# CamController3.net
KiCad netlist of a schematic drawn in Altium Designer
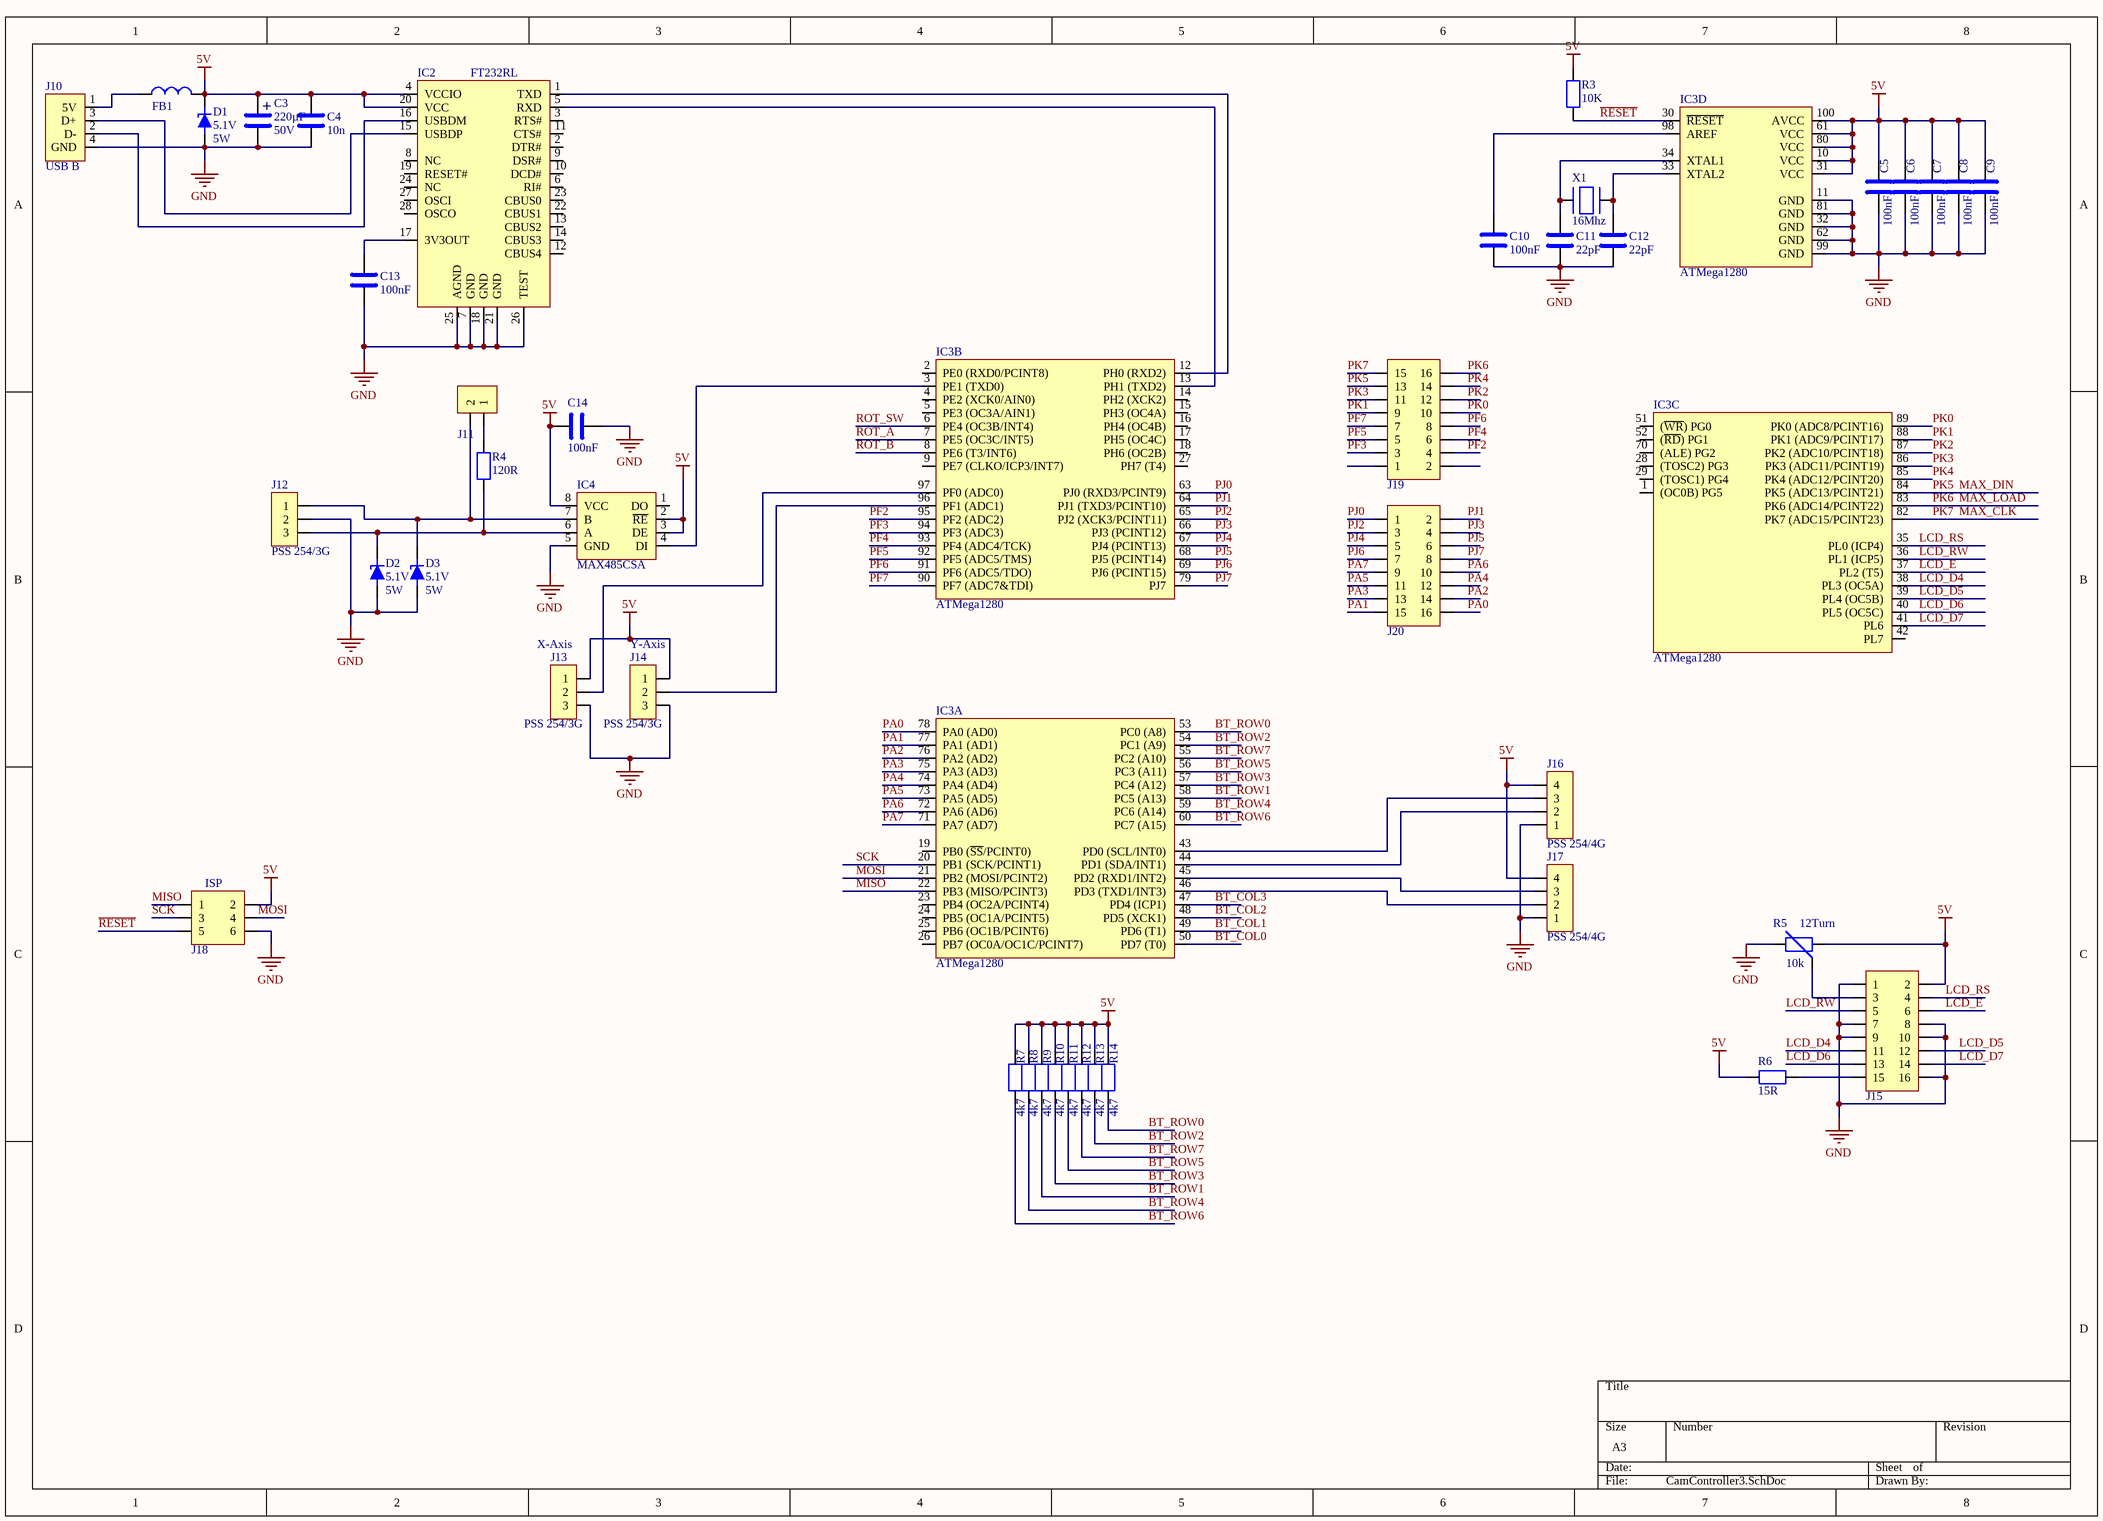
[diagram p0: CamController3.SchDoc]

(export (version "E")
  (design (tool "Eeschema 10.0.6"))
  (components
    (comp (ref "C3")
      (value "220µF")
      (footprint "RM5D125H20")
      (description "nichicon")
      (fields (field (name "VOLTAGE") "50V") (field (name "Comment") "Elko_220uF_50V"))
      (libsource (lib "elkos") (part "Elko_220uF_50V"))
    )
    (comp (ref "C4")
      (value "10n")
      (footprint "0805")
      (description "10nF 50V MLCC 0805")
      (fields (field (name "VOLTAGE") "50V"))
      (libsource (lib "capacitors") (part "10nF 50V MLCC 0805"))
    )
    (comp (ref "C5")
      (value "100nF")
      (footprint "0805")
      (description "100nF 50V MLCC 0805")
      (fields (field (name "VOLTAGE") "50V"))
      (libsource (lib "capacitors") (part "100nF 50V MLCC 0805"))
    )
    (comp (ref "C6")
      (value "100nF")
      (footprint "0805")
      (description "100nF 50V MLCC 0805")
      (fields (field (name "VOLTAGE") "50V"))
      (libsource (lib "capacitors") (part "100nF 50V MLCC 0805"))
    )
    (comp (ref "C7")
      (value "100nF")
      (footprint "0805")
      (description "100nF 50V MLCC 0805")
      (fields (field (name "VOLTAGE") "50V"))
      (libsource (lib "capacitors") (part "100nF 50V MLCC 0805"))
    )
    (comp (ref "C8")
      (value "100nF")
      (footprint "0805")
      (description "100nF 50V MLCC 0805")
      (fields (field (name "VOLTAGE") "50V"))
      (libsource (lib "capacitors") (part "100nF 50V MLCC 0805"))
    )
    (comp (ref "C9")
      (value "100nF")
      (footprint "0805")
      (description "100nF 50V MLCC 0805")
      (fields (field (name "VOLTAGE") "50V"))
      (libsource (lib "capacitors") (part "100nF 50V MLCC 0805"))
    )
    (comp (ref "C10")
      (value "100nF")
      (footprint "0805")
      (description "100nF 50V MLCC 0805")
      (fields (field (name "VOLTAGE") "50V"))
      (libsource (lib "capacitors") (part "100nF 50V MLCC 0805"))
    )
    (comp (ref "C11")
      (value "22pF")
      (footprint "0805")
      (description "22pF 50V MLCC 0805")
      (fields (field (name "VOLTAGE") "50V"))
      (libsource (lib "capacitors") (part "22pF 50V MLCC 0805"))
    )
    (comp (ref "C12")
      (value "22pF")
      (footprint "0805")
      (description "22pF 50V MLCC 0805")
      (fields (field (name "VOLTAGE") "50V"))
      (libsource (lib "capacitors") (part "22pF 50V MLCC 0805"))
    )
    (comp (ref "C13")
      (value "100nF")
      (footprint "0805")
      (description "100nF 50V MLCC 0805")
      (fields (field (name "VOLTAGE") "50V"))
      (libsource (lib "capacitors") (part "100nF 50V MLCC 0805"))
    )
    (comp (ref "C14")
      (value "100nF")
      (footprint "0805")
      (description "100nF 50V MLCC 0805")
      (fields (field (name "VOLTAGE") "50V"))
      (libsource (lib "capacitors") (part "100nF 50V MLCC 0805"))
    )
    (comp (ref "D1")
      (value "ZD-5W 5,1V")
      (footprint "DO-204AF")
      (fields (field (name "VOLTAGE") "5.1V") (field (name "POWER") "5W"))
      (libsource (lib "diodes") (part "ZD-5W 5,1V"))
    )
    (comp (ref "D2")
      (value "ZD-5W 5,1V")
      (footprint "DO-204AF")
      (fields (field (name "VOLTAGE") "5.1V") (field (name "POWER") "5W"))
      (libsource (lib "diodes") (part "ZD-5W 5,1V"))
    )
    (comp (ref "D3")
      (value "ZD-5W 5,1V")
      (footprint "DO-204AF")
      (fields (field (name "VOLTAGE") "5.1V") (field (name "POWER") "5W"))
      (libsource (lib "diodes") (part "ZD-5W 5,1V"))
    )
    (comp (ref "FB1")
      (value "Feritbead")
      (footprint "Ferritbead")
      (libsource (lib "misc") (part "Feritbead"))
    )
    (comp (ref "IC2")
      (value "FT232RL")
      (footprint "SSOP-28")
      (description "USB UART Bridge")
      (libsource (lib "misc") (part "FT 232 RL"))
    )
    (comp (ref "IC3")
      (value "ATMega1280")
      (footprint "LQFP100")
      (libsource (lib "microcontroller") (part "ATmega1280"))
    )
    (comp (ref "IC4")
      (value "MAX485CSA")
      (footprint "SOIC8")
      (description "RS485 driver")
      (libsource (lib "misc") (part "MAX485CSA"))
    )
    (comp (ref "J10") (value "USB B") (footprint "USB_B") (libsource (lib "connectors_pc") (part "USB_B")))
    (comp (ref "J11")
      (value "SL 1X2G 2,54")
      (footprint "SL_1x2 2.54mm")
      (description "Stiftleiste 2pol 2.54mm")
      (libsource (lib "connectors_sl") (part "SL 1X2G 2,54"))
    )
    (comp (ref "J12")
      (value "PSS 254/3G")
      (footprint "PSS 3pol")
      (description "PSS 3pol wire-to-board-connector")
      (libsource (lib "connectors_pss") (part "PSS 254/3G"))
    )
    (comp (ref "J13")
      (value "PSS 254/3G")
      (footprint "PSS 3pol")
      (description "PSS 3pol wire-to-board-connector")
      (libsource (lib "connectors_pss") (part "PSS 254/3G"))
    )
    (comp (ref "J14")
      (value "PSS 254/3G")
      (footprint "PSS 3pol")
      (description "PSS 3pol wire-to-board-connector")
      (libsource (lib "connectors_pss") (part "PSS 254/3G"))
    )
    (comp (ref "J15")
      (value "Wannenstecker 16pol 2,54mm")
      (footprint "WSL16G")
      (libsource (lib "wannenstecker") (part "Wannenstecker 16pol 2,54mm"))
    )
    (comp (ref "J16")
      (value "PSS 254/4G")
      (footprint "PSS 4pol")
      (description "PSS 4pol wire-to-board-connector")
      (libsource (lib "connectors_pss") (part "PSS 254/4G"))
    )
    (comp (ref "J17")
      (value "PSS 254/4G")
      (footprint "PSS 4pol")
      (description "PSS 4pol wire-to-board-connector")
      (libsource (lib "connectors_pss") (part "PSS 254/4G"))
    )
    (comp (ref "J18")
      (value "Wannenstecker 6pol 2,54mm")
      (footprint "WSL6G")
      (libsource (lib "wannenstecker") (part "Wannenstecker 6pol 2,54mm"))
    )
    (comp (ref "J19")
      (value "Wannenstecker 16pol 2,54mm")
      (footprint "WSL16G")
      (libsource (lib "") (part "Wannenstecker 16pol 2,54mm_1"))
    )
    (comp (ref "J20")
      (value "Wannenstecker 16pol 2,54mm")
      (footprint "WSL16G")
      (libsource (lib "wannenstecker") (part "Wannenstecker 16pol 2,54mm"))
    )
    (comp (ref "R3")
      (value "10K")
      (footprint "res0805")
      (description "10K 125mW 0805")
      (fields (field (name "TOLERANCE") "1%"))
      (libsource (lib "resistors") (part "10K 125mW 0805"))
    )
    (comp (ref "R4")
      (value "120R")
      (footprint "res0805")
      (description "120R 125mW 0805")
      (fields (field (name "TOLERANCE") "1%"))
      (libsource (lib "resistors") (part "120R 125mW 0805"))
    )
    (comp (ref "R5")
      (value "12Turn")
      (footprint "64W")
      (description "trimmer 12turn")
      (fields (field (name "ALTIUM_VALUE") "10k"))
      (libsource (lib "trimmer") (part "64W-10K"))
    )
    (comp (ref "R6")
      (value "15R")
      (footprint "res0805")
      (description "15R 125mW 0805")
      (fields (field (name "TOLERANCE") "1%"))
      (libsource (lib "resistors") (part "15R 125mW 0805"))
    )
    (comp (ref "R7")
      (value "4k7")
      (footprint "res0805")
      (description "4k7 125mW 0805")
      (fields (field (name "TOLERANCE") "1%"))
      (libsource (lib "resistors") (part "4k7 125mW 0805"))
    )
    (comp (ref "R8")
      (value "4k7")
      (footprint "res0805")
      (description "4k7 125mW 0805")
      (fields (field (name "TOLERANCE") "1%"))
      (libsource (lib "resistors") (part "4k7 125mW 0805"))
    )
    (comp (ref "R9")
      (value "4k7")
      (footprint "res0805")
      (description "4k7 125mW 0805")
      (fields (field (name "TOLERANCE") "1%"))
      (libsource (lib "resistors") (part "4k7 125mW 0805"))
    )
    (comp (ref "R10")
      (value "4k7")
      (footprint "res0805")
      (description "4k7 125mW 0805")
      (fields (field (name "TOLERANCE") "1%"))
      (libsource (lib "resistors") (part "4k7 125mW 0805"))
    )
    (comp (ref "R11")
      (value "4k7")
      (footprint "res0805")
      (description "4k7 125mW 0805")
      (fields (field (name "TOLERANCE") "1%"))
      (libsource (lib "resistors") (part "4k7 125mW 0805"))
    )
    (comp (ref "R12")
      (value "4k7")
      (footprint "res0805")
      (description "4k7 125mW 0805")
      (fields (field (name "TOLERANCE") "1%"))
      (libsource (lib "resistors") (part "4k7 125mW 0805"))
    )
    (comp (ref "R13")
      (value "4k7")
      (footprint "res0805")
      (description "4k7 125mW 0805")
      (fields (field (name "TOLERANCE") "1%"))
      (libsource (lib "resistors") (part "4k7 125mW 0805"))
    )
    (comp (ref "R14")
      (value "4k7")
      (footprint "res0805")
      (description "4k7 125mW 0805")
      (fields (field (name "TOLERANCE") "1%"))
      (libsource (lib "resistors") (part "4k7 125mW 0805"))
    )
    (comp (ref "X1")
      (value "8Mhz_HC49U")
      (footprint "HC49")
      (description "8Mhz crystal resonator")
      (fields (field (name "FREQUENCY") "16Mhz"))
      (libsource (lib "crystals") (part "8Mhz_HC49U"))
    )
  )
  (nets
    (net (code "1") (name "/BT_COL0") (class "Default")
      (node (ref "IC3") (pin "50") (pinfunction "PD7_(T0)_50") (pintype "passive"))
    )
    (net (code "2") (name "/BT_COL1") (class "Default")
      (node (ref "IC3") (pin "49") (pinfunction "PD6_(T1)_49") (pintype "passive"))
    )
    (net (code "3") (name "/BT_COL2") (class "Default")
      (node (ref "IC3") (pin "48") (pinfunction "PD5_(XCK1)_48") (pintype "passive"))
    )
    (net (code "4") (name "/BT_COL3") (class "Default")
      (node (ref "IC3") (pin "47") (pinfunction "PD4_(ICP1)_47") (pintype "passive"))
    )
    (net (code "5") (name "/BT_ROW0") (class "Default")
      (node (ref "IC3") (pin "53") (pinfunction "PC0_(A8)_53") (pintype "passive"))
      (node (ref "R14") (pin "1") (pinfunction "1_1") (pintype "passive"))
    )
    (net (code "6") (name "/BT_ROW1") (class "Default")
      (node (ref "IC3") (pin "58") (pinfunction "PC5_(A13)_58") (pintype "passive"))
      (node (ref "R9") (pin "1") (pinfunction "1_1") (pintype "passive"))
    )
    (net (code "7") (name "/BT_ROW2") (class "Default")
      (node (ref "IC3") (pin "54") (pinfunction "PC1_(A9)_54") (pintype "passive"))
      (node (ref "R13") (pin "1") (pinfunction "1_1") (pintype "passive"))
    )
    (net (code "8") (name "/BT_ROW3") (class "Default")
      (node (ref "IC3") (pin "57") (pinfunction "PC4_(A12)_57") (pintype "passive"))
      (node (ref "R10") (pin "1") (pinfunction "1_1") (pintype "passive"))
    )
    (net (code "9") (name "/BT_ROW4") (class "Default")
      (node (ref "IC3") (pin "59") (pinfunction "PC6_(A14)_59") (pintype "passive"))
      (node (ref "R8") (pin "1") (pinfunction "1_1") (pintype "passive"))
    )
    (net (code "10") (name "/BT_ROW5") (class "Default")
      (node (ref "IC3") (pin "56") (pinfunction "PC3_(A11)_56") (pintype "passive"))
      (node (ref "R11") (pin "1") (pinfunction "1_1") (pintype "passive"))
    )
    (net (code "11") (name "/BT_ROW6") (class "Default")
      (node (ref "IC3") (pin "60") (pinfunction "PC7_(A15)_60") (pintype "passive"))
      (node (ref "R7") (pin "1") (pinfunction "1_1") (pintype "passive"))
    )
    (net (code "12") (name "/BT_ROW7") (class "Default")
      (node (ref "IC3") (pin "55") (pinfunction "PC2_(A10)_55") (pintype "passive"))
      (node (ref "R12") (pin "1") (pinfunction "1_1") (pintype "passive"))
    )
    (net (code "13") (name "/LCD_D4") (class "Default")
      (node (ref "IC3") (pin "38") (pinfunction "PL3_(OC5A)_38") (pintype "passive"))
      (node (ref "J15") (pin "11") (pinfunction "11_11") (pintype "passive"))
    )
    (net (code "14") (name "/LCD_D5") (class "Default")
      (node (ref "IC3") (pin "39") (pinfunction "PL4_(OC5B)_39") (pintype "passive"))
      (node (ref "J15") (pin "12") (pinfunction "12_12") (pintype "passive"))
    )
    (net (code "15") (name "/LCD_D6") (class "Default")
      (node (ref "IC3") (pin "40") (pinfunction "PL5_(OC5C)_40") (pintype "passive"))
      (node (ref "J15") (pin "13") (pinfunction "13_13") (pintype "passive"))
    )
    (net (code "16") (name "/LCD_D7") (class "Default")
      (node (ref "IC3") (pin "41") (pinfunction "PL6_41") (pintype "passive"))
      (node (ref "J15") (pin "14") (pinfunction "14_14") (pintype "passive"))
    )
    (net (code "17") (name "/LCD_E") (class "Default")
      (node (ref "IC3") (pin "37") (pinfunction "PL2_(T5)_37") (pintype "passive"))
      (node (ref "J15") (pin "6") (pinfunction "6_6") (pintype "passive"))
    )
    (net (code "18") (name "/LCD_RS") (class "Default")
      (node (ref "IC3") (pin "35") (pinfunction "PL0_(ICP4)_35") (pintype "passive"))
      (node (ref "J15") (pin "4") (pinfunction "4_4") (pintype "passive"))
    )
    (net (code "19") (name "/LCD_RW") (class "Default")
      (node (ref "IC3") (pin "36") (pinfunction "PL1_(ICP5)_36") (pintype "passive"))
      (node (ref "J15") (pin "5") (pinfunction "5_5") (pintype "passive"))
    )
    (net (code "20") (name "/MAX_CLK") (class "Default")
      (node (ref "IC3") (pin "82") (pinfunction "PK7_(ADC15/PCINT23)_82") (pintype "passive"))
      (node (ref "J19") (pin "15") (pinfunction "15_15") (pintype "passive"))
    )
    (net (code "21") (name "/MAX_DIN") (class "Default")
      (node (ref "IC3") (pin "84") (pinfunction "PK5_(ADC13/PCINT21)_84") (pintype "passive"))
      (node (ref "J19") (pin "13") (pinfunction "13_13") (pintype "passive"))
    )
    (net (code "22") (name "/MAX_LOAD") (class "Default")
      (node (ref "IC3") (pin "83") (pinfunction "PK6_(ADC14/PCINT22)_83") (pintype "passive"))
      (node (ref "J19") (pin "16") (pinfunction "16_16") (pintype "passive"))
    )
    (net (code "23") (name "/MISO") (class "Default")
      (node (ref "IC3") (pin "22") (pinfunction "PB3_(MISO/PCINT3)_22") (pintype "passive"))
      (node (ref "J18") (pin "1") (pinfunction "1_1") (pintype "passive"))
    )
    (net (code "24") (name "/MOSI") (class "Default")
      (node (ref "IC3") (pin "21") (pinfunction "PB2_(MOSI/PCINT2)_21") (pintype "passive"))
      (node (ref "J18") (pin "4") (pinfunction "4_4") (pintype "passive"))
    )
    (net (code "25") (name "/PA0") (class "Default")
      (node (ref "IC3") (pin "78") (pinfunction "PA0_(AD0)_78") (pintype "passive"))
      (node (ref "J20") (pin "16") (pinfunction "16_16") (pintype "passive"))
    )
    (net (code "26") (name "/PA1") (class "Default")
      (node (ref "IC3") (pin "77") (pinfunction "PA1_(AD1)_77") (pintype "passive"))
      (node (ref "J20") (pin "15") (pinfunction "15_15") (pintype "passive"))
    )
    (net (code "27") (name "/PA2") (class "Default")
      (node (ref "IC3") (pin "76") (pinfunction "PA2_(AD2)_76") (pintype "passive"))
      (node (ref "J20") (pin "14") (pinfunction "14_14") (pintype "passive"))
    )
    (net (code "28") (name "/PA3") (class "Default")
      (node (ref "IC3") (pin "75") (pinfunction "PA3_(AD3)_75") (pintype "passive"))
      (node (ref "J20") (pin "13") (pinfunction "13_13") (pintype "passive"))
    )
    (net (code "29") (name "/PA4") (class "Default")
      (node (ref "IC3") (pin "74") (pinfunction "PA4_(AD4)_74") (pintype "passive"))
      (node (ref "J20") (pin "12") (pinfunction "12_12") (pintype "passive"))
    )
    (net (code "30") (name "/PA5") (class "Default")
      (node (ref "IC3") (pin "73") (pinfunction "PA5_(AD5)_73") (pintype "passive"))
      (node (ref "J20") (pin "11") (pinfunction "11_11") (pintype "passive"))
    )
    (net (code "31") (name "/PA6") (class "Default")
      (node (ref "IC3") (pin "72") (pinfunction "PA6_(AD6)_72") (pintype "passive"))
      (node (ref "J20") (pin "10") (pinfunction "10_10") (pintype "passive"))
    )
    (net (code "32") (name "/PA7") (class "Default")
      (node (ref "IC3") (pin "71") (pinfunction "PA7_(AD7)_71") (pintype "passive"))
      (node (ref "J20") (pin "9") (pinfunction "9_9") (pintype "passive"))
    )
    (net (code "33") (name "/PF2") (class "Default")
      (node (ref "IC3") (pin "95") (pinfunction "PF2_(ADC2)_95") (pintype "passive"))
      (node (ref "J19") (pin "4") (pinfunction "4_4") (pintype "passive"))
    )
    (net (code "34") (name "/PF3") (class "Default")
      (node (ref "IC3") (pin "94") (pinfunction "PF3_(ADC3)_94") (pintype "passive"))
      (node (ref "J19") (pin "3") (pinfunction "3_3") (pintype "passive"))
    )
    (net (code "35") (name "/PF4") (class "Default")
      (node (ref "IC3") (pin "93") (pinfunction "PF4_(ADC4/TCK)_93") (pintype "passive"))
      (node (ref "J19") (pin "6") (pinfunction "6_6") (pintype "passive"))
    )
    (net (code "36") (name "/PF5") (class "Default")
      (node (ref "IC3") (pin "92") (pinfunction "PF5_(ADC5/TMS)_92") (pintype "passive"))
      (node (ref "J19") (pin "5") (pinfunction "5_5") (pintype "passive"))
    )
    (net (code "37") (name "/PF6") (class "Default")
      (node (ref "IC3") (pin "91") (pinfunction "PF6_(ADC5/TDO)_91") (pintype "passive"))
      (node (ref "J19") (pin "8") (pinfunction "8_8") (pintype "passive"))
    )
    (net (code "38") (name "/PF7") (class "Default")
      (node (ref "IC3") (pin "90") (pinfunction "PF7_(ADC7&TDI)_90") (pintype "passive"))
      (node (ref "J19") (pin "7") (pinfunction "7_7") (pintype "passive"))
    )
    (net (code "39") (name "/PJ0") (class "Default")
      (node (ref "IC3") (pin "63") (pinfunction "PJ0_(RXD3/PCINT9)_63") (pintype "passive"))
      (node (ref "J20") (pin "1") (pinfunction "1_1") (pintype "passive"))
    )
    (net (code "40") (name "/PJ1") (class "Default")
      (node (ref "IC3") (pin "64") (pinfunction "PJ1_(TXD3/PCINT10)_64") (pintype "passive"))
      (node (ref "J20") (pin "2") (pinfunction "2_2") (pintype "passive"))
    )
    (net (code "41") (name "/PJ2") (class "Default")
      (node (ref "IC3") (pin "65") (pinfunction "PJ2_(XCK3/PCINT11)_65") (pintype "passive"))
      (node (ref "J20") (pin "3") (pinfunction "3_3") (pintype "passive"))
    )
    (net (code "42") (name "/PJ3") (class "Default")
      (node (ref "IC3") (pin "66") (pinfunction "PJ3_(PCINT12)_66") (pintype "passive"))
      (node (ref "J20") (pin "4") (pinfunction "4_4") (pintype "passive"))
    )
    (net (code "43") (name "/PJ4") (class "Default")
      (node (ref "IC3") (pin "67") (pinfunction "PJ4_(PCINT13)_67") (pintype "passive"))
      (node (ref "J20") (pin "5") (pinfunction "5_5") (pintype "passive"))
    )
    (net (code "44") (name "/PJ5") (class "Default")
      (node (ref "IC3") (pin "68") (pinfunction "PJ5_(PCINT14)_68") (pintype "passive"))
      (node (ref "J20") (pin "6") (pinfunction "6_6") (pintype "passive"))
    )
    (net (code "45") (name "/PJ6") (class "Default")
      (node (ref "IC3") (pin "69") (pinfunction "PJ6_(PCINT15)_69") (pintype "passive"))
      (node (ref "J20") (pin "7") (pinfunction "7_7") (pintype "passive"))
    )
    (net (code "46") (name "/PJ7") (class "Default")
      (node (ref "IC3") (pin "79") (pinfunction "PJ7_79") (pintype "passive"))
      (node (ref "J20") (pin "8") (pinfunction "8_8") (pintype "passive"))
    )
    (net (code "47") (name "/PK0") (class "Default")
      (node (ref "IC3") (pin "89") (pinfunction "PK0_(ADC8/PCINT16)_89") (pintype "passive"))
      (node (ref "J19") (pin "10") (pinfunction "10_10") (pintype "passive"))
    )
    (net (code "48") (name "/PK1") (class "Default")
      (node (ref "IC3") (pin "88") (pinfunction "PK1_(ADC9/PCINT17)_88") (pintype "passive"))
      (node (ref "J19") (pin "9") (pinfunction "9_9") (pintype "passive"))
    )
    (net (code "49") (name "/PK2") (class "Default")
      (node (ref "IC3") (pin "87") (pinfunction "PK2_(ADC10/PCINT18)_87") (pintype "passive"))
      (node (ref "J19") (pin "12") (pinfunction "12_12") (pintype "passive"))
    )
    (net (code "50") (name "/PK3") (class "Default")
      (node (ref "IC3") (pin "86") (pinfunction "PK3_(ADC11/PCINT19)_86") (pintype "passive"))
      (node (ref "J19") (pin "11") (pinfunction "11_11") (pintype "passive"))
    )
    (net (code "51") (name "/PK4") (class "Default")
      (node (ref "IC3") (pin "85") (pinfunction "PK4_(ADC12/PCINT20)_85") (pintype "passive"))
      (node (ref "J19") (pin "14") (pinfunction "14_14") (pintype "passive"))
    )
    (net (code "52") (name "/ROT_A") (class "Default")
      (node (ref "IC3") (pin "7") (pinfunction "PE5_(OC3C/INT5)_7") (pintype "passive"))
    )
    (net (code "53") (name "/ROT_B") (class "Default")
      (node (ref "IC3") (pin "8") (pinfunction "PE6_(T3/INT6)_8") (pintype "passive"))
    )
    (net (code "54") (name "/ROT_SW") (class "Default")
      (node (ref "IC3") (pin "6") (pinfunction "PE4_(OC3B/INT4)_6") (pintype "passive"))
    )
    (net (code "55") (name "/SCK") (class "Default")
      (node (ref "IC3") (pin "20") (pinfunction "PB1_(SCK/PCINT1)_20") (pintype "passive"))
      (node (ref "J18") (pin "3") (pinfunction "3_3") (pintype "passive"))
    )
    (net (code "56") (name "/~{RESET}") (class "Default")
      (node (ref "IC3") (pin "30") (pinfunction "~{RESET}_30") (pintype "passive"))
      (node (ref "J18") (pin "5") (pinfunction "5_5") (pintype "passive"))
      (node (ref "R3") (pin "1") (pinfunction "1_1") (pintype "passive"))
    )
    (net (code "57") (name "5V") (class "Default")
      (node (ref "C14") (pin "1") (pinfunction "1_1") (pintype "passive"))
      (node (ref "C3") (pin "+") (pinfunction "+_+") (pintype "passive"))
      (node (ref "C4") (pin "1") (pinfunction "1_1") (pintype "passive"))
      (node (ref "C5") (pin "2") (pinfunction "2_2") (pintype "passive"))
      (node (ref "C6") (pin "2") (pinfunction "2_2") (pintype "passive"))
      (node (ref "C7") (pin "2") (pinfunction "2_2") (pintype "passive"))
      (node (ref "C8") (pin "2") (pinfunction "2_2") (pintype "passive"))
      (node (ref "C9") (pin "2") (pinfunction "2_2") (pintype "passive"))
      (node (ref "D1") (pin "1") (pinfunction "1_1") (pintype "passive"))
      (node (ref "FB1") (pin "2") (pinfunction "2_2") (pintype "passive"))
      (node (ref "IC2") (pin "20") (pinfunction "VCC_20") (pintype "passive"))
      (node (ref "IC2") (pin "4") (pinfunction "VCCIO_4") (pintype "passive"))
      (node (ref "IC3") (pin "10") (pinfunction "VCC_10") (pintype "passive"))
      (node (ref "IC3") (pin "100") (pinfunction "AVCC_100") (pintype "passive"))
      (node (ref "IC3") (pin "31") (pinfunction "VCC_31") (pintype "passive"))
      (node (ref "IC3") (pin "61") (pinfunction "VCC_61") (pintype "passive"))
      (node (ref "IC3") (pin "80") (pinfunction "VCC_80") (pintype "passive"))
      (node (ref "IC4") (pin "2") (pinfunction "~{RE}_2") (pintype "passive"))
      (node (ref "IC4") (pin "3") (pinfunction "DE_3") (pintype "passive"))
      (node (ref "IC4") (pin "8") (pinfunction "VCC_8") (pintype "passive"))
      (node (ref "J13") (pin "1") (pinfunction "1_1") (pintype "passive"))
      (node (ref "J14") (pin "1") (pinfunction "1_1") (pintype "passive"))
      (node (ref "J15") (pin "2") (pinfunction "2_2") (pintype "passive"))
      (node (ref "J16") (pin "4") (pinfunction "4_4") (pintype "passive"))
      (node (ref "J17") (pin "4") (pinfunction "4_4") (pintype "passive"))
      (node (ref "J18") (pin "2") (pinfunction "2_2") (pintype "passive"))
      (node (ref "R10") (pin "2") (pinfunction "2_2") (pintype "passive"))
      (node (ref "R11") (pin "2") (pinfunction "2_2") (pintype "passive"))
      (node (ref "R12") (pin "2") (pinfunction "2_2") (pintype "passive"))
      (node (ref "R13") (pin "2") (pinfunction "2_2") (pintype "passive"))
      (node (ref "R14") (pin "2") (pinfunction "2_2") (pintype "passive"))
      (node (ref "R3") (pin "2") (pinfunction "2_2") (pintype "passive"))
      (node (ref "R5") (pin "3") (pinfunction "3_3") (pintype "passive"))
      (node (ref "R6") (pin "2") (pinfunction "2_2") (pintype "passive"))
      (node (ref "R7") (pin "2") (pinfunction "2_2") (pintype "passive"))
      (node (ref "R8") (pin "2") (pinfunction "2_2") (pintype "passive"))
      (node (ref "R9") (pin "2") (pinfunction "2_2") (pintype "passive"))
    )
    (net (code "58") (name "GND") (class "Default")
      (node (ref "C10") (pin "1") (pinfunction "1_1") (pintype "passive"))
      (node (ref "C11") (pin "2") (pinfunction "2_2") (pintype "passive"))
      (node (ref "C12") (pin "2") (pinfunction "2_2") (pintype "passive"))
      (node (ref "C13") (pin "2") (pinfunction "2_2") (pintype "passive"))
      (node (ref "C14") (pin "2") (pinfunction "2_2") (pintype "passive"))
      (node (ref "C3") (pin "-") (pinfunction "-_-") (pintype "passive"))
      (node (ref "C4") (pin "2") (pinfunction "2_2") (pintype "passive"))
      (node (ref "C5") (pin "1") (pinfunction "1_1") (pintype "passive"))
      (node (ref "C6") (pin "1") (pinfunction "1_1") (pintype "passive"))
      (node (ref "C7") (pin "1") (pinfunction "1_1") (pintype "passive"))
      (node (ref "C8") (pin "1") (pinfunction "1_1") (pintype "passive"))
      (node (ref "C9") (pin "1") (pinfunction "1_1") (pintype "passive"))
      (node (ref "D1") (pin "2") (pinfunction "2_2") (pintype "passive"))
      (node (ref "D2") (pin "2") (pinfunction "2_2") (pintype "passive"))
      (node (ref "D3") (pin "2") (pinfunction "2_2") (pintype "passive"))
      (node (ref "IC2") (pin "18") (pinfunction "GND_18") (pintype "passive"))
      (node (ref "IC2") (pin "21") (pinfunction "GND_21") (pintype "passive"))
      (node (ref "IC2") (pin "25") (pinfunction "AGND_25") (pintype "passive"))
      (node (ref "IC2") (pin "26") (pinfunction "TEST_26") (pintype "passive"))
      (node (ref "IC2") (pin "7") (pinfunction "GND_7") (pintype "passive"))
      (node (ref "IC3") (pin "11") (pinfunction "GND_11") (pintype "passive"))
      (node (ref "IC3") (pin "32") (pinfunction "GND_32") (pintype "passive"))
      (node (ref "IC3") (pin "62") (pinfunction "GND_62") (pintype "passive"))
      (node (ref "IC3") (pin "81") (pinfunction "GND_81") (pintype "passive"))
      (node (ref "IC3") (pin "99") (pinfunction "GND_99") (pintype "passive"))
      (node (ref "IC4") (pin "5") (pinfunction "GND_5") (pintype "passive"))
      (node (ref "J10") (pin "4") (pinfunction "GND_4") (pintype "passive"))
      (node (ref "J12") (pin "2") (pinfunction "2_2") (pintype "passive"))
      (node (ref "J13") (pin "3") (pinfunction "3_3") (pintype "passive"))
      (node (ref "J14") (pin "3") (pinfunction "3_3") (pintype "passive"))
      (node (ref "J15") (pin "1") (pinfunction "1_1") (pintype "passive"))
      (node (ref "J15") (pin "10") (pinfunction "10_10") (pintype "passive"))
      (node (ref "J15") (pin "16") (pinfunction "16_16") (pintype "passive"))
      (node (ref "J15") (pin "7") (pinfunction "7_7") (pintype "passive"))
      (node (ref "J15") (pin "8") (pinfunction "8_8") (pintype "passive"))
      (node (ref "J15") (pin "9") (pinfunction "9_9") (pintype "passive"))
      (node (ref "J16") (pin "1") (pinfunction "1_1") (pintype "passive"))
      (node (ref "J17") (pin "1") (pinfunction "1_1") (pintype "passive"))
      (node (ref "J18") (pin "6") (pinfunction "6_6") (pintype "passive"))
      (node (ref "R5") (pin "1") (pinfunction "1_1") (pintype "passive"))
    )
    (net (code "59") (name "Net-(IC2-3V3OUT)") (class "Default")
      (node (ref "C13") (pin "1") (pinfunction "1_1") (pintype "passive"))
      (node (ref "IC2") (pin "17") (pinfunction "3V3OUT_17") (pintype "passive"))
    )
    (net (code "60") (name "Net-(IC2-RXD)") (class "Default")
      (node (ref "IC2") (pin "5") (pinfunction "RXD_5") (pintype "passive"))
      (node (ref "IC3") (pin "13") (pinfunction "PH1_(TXD2)_13") (pintype "passive"))
    )
    (net (code "61") (name "Net-(IC2-TXD)") (class "Default")
      (node (ref "IC2") (pin "1") (pinfunction "TXD_1") (pintype "passive"))
      (node (ref "IC3") (pin "12") (pinfunction "PH0_(RXD2)_12") (pintype "passive"))
    )
    (net (code "62") (name "Net-(IC2-USBDM)") (class "Default")
      (node (ref "IC2") (pin "16") (pinfunction "USBDM_16") (pintype "passive"))
      (node (ref "J10") (pin "2") (pinfunction "D-_2") (pintype "passive"))
    )
    (net (code "63") (name "Net-(IC2-USBDP)") (class "Default")
      (node (ref "IC2") (pin "15") (pinfunction "USBDP_15") (pintype "passive"))
      (node (ref "J10") (pin "3") (pinfunction "D+_3") (pintype "passive"))
    )
    (net (code "64") (name "Net-(IC3A-PD0_(SCL{slash}INT0))") (class "Default")
      (node (ref "IC3") (pin "43") (pinfunction "PD0_(SCL/INT0)_43") (pintype "passive"))
      (node (ref "J16") (pin "3") (pinfunction "3_3") (pintype "passive"))
    )
    (net (code "65") (name "Net-(IC3A-PD1_(SDA{slash}INT1))") (class "Default")
      (node (ref "IC3") (pin "44") (pinfunction "PD1_(SDA/INT1)_44") (pintype "passive"))
      (node (ref "J16") (pin "2") (pinfunction "2_2") (pintype "passive"))
    )
    (net (code "66") (name "Net-(IC3A-PD2_(RXD1{slash}INT2))") (class "Default")
      (node (ref "IC3") (pin "45") (pinfunction "PD2_(RXD1/INT2)_45") (pintype "passive"))
      (node (ref "J17") (pin "3") (pinfunction "3_3") (pintype "passive"))
    )
    (net (code "67") (name "Net-(IC3A-PD3_(TXD1{slash}INT3))") (class "Default")
      (node (ref "IC3") (pin "46") (pinfunction "PD3_(TXD1/INT3)_46") (pintype "passive"))
      (node (ref "J17") (pin "2") (pinfunction "2_2") (pintype "passive"))
    )
    (net (code "68") (name "Net-(IC3B-PE1_(TXD0))") (class "Default")
      (node (ref "IC3") (pin "3") (pinfunction "PE1_(TXD0)_3") (pintype "passive"))
      (node (ref "IC4") (pin "4") (pinfunction "DI_4") (pintype "passive"))
    )
    (net (code "69") (name "Net-(IC3B-PF0_(ADC0))") (class "Default")
      (node (ref "IC3") (pin "97") (pinfunction "PF0_(ADC0)_97") (pintype "passive"))
      (node (ref "J13") (pin "2") (pinfunction "2_2") (pintype "passive"))
    )
    (net (code "70") (name "Net-(IC3B-PF1_(ADC1))") (class "Default")
      (node (ref "IC3") (pin "96") (pinfunction "PF1_(ADC1)_96") (pintype "passive"))
      (node (ref "J14") (pin "2") (pinfunction "2_2") (pintype "passive"))
    )
    (net (code "71") (name "Net-(IC3D-AREF)") (class "Default")
      (node (ref "C10") (pin "2") (pinfunction "2_2") (pintype "passive"))
      (node (ref "IC3") (pin "98") (pinfunction "AREF_98") (pintype "passive"))
    )
    (net (code "72") (name "Net-(IC3D-XTAL1)") (class "Default")
      (node (ref "C11") (pin "1") (pinfunction "1_1") (pintype "passive"))
      (node (ref "IC3") (pin "34") (pinfunction "XTAL1_34") (pintype "passive"))
      (node (ref "X1") (pin "1") (pinfunction "1_1") (pintype "passive"))
    )
    (net (code "73") (name "Net-(IC3D-XTAL2)") (class "Default")
      (node (ref "C12") (pin "1") (pinfunction "1_1") (pintype "passive"))
      (node (ref "IC3") (pin "33") (pinfunction "XTAL2_33") (pintype "passive"))
      (node (ref "X1") (pin "2") (pinfunction "2_2") (pintype "passive"))
    )
    (net (code "74") (name "Net-(IC4-A)") (class "Default")
      (node (ref "D2") (pin "1") (pinfunction "1_1") (pintype "passive"))
      (node (ref "IC4") (pin "6") (pinfunction "A_6") (pintype "passive"))
      (node (ref "J12") (pin "3") (pinfunction "3_3") (pintype "passive"))
      (node (ref "R4") (pin "1") (pinfunction "1_1") (pintype "passive"))
    )
    (net (code "75") (name "Net-(IC4-B)") (class "Default")
      (node (ref "D3") (pin "1") (pinfunction "1_1") (pintype "passive"))
      (node (ref "IC4") (pin "7") (pinfunction "B_7") (pintype "passive"))
      (node (ref "J11") (pin "2") (pinfunction "2_2") (pintype "passive"))
      (node (ref "J12") (pin "1") (pinfunction "1_1") (pintype "passive"))
    )
    (net (code "76") (name "Net-(J10-5V)") (class "Default")
      (node (ref "FB1") (pin "1") (pinfunction "1_1") (pintype "passive"))
      (node (ref "J10") (pin "1") (pinfunction "5V_1") (pintype "passive"))
    )
    (net (code "77") (name "Net-(J11-Pad1)") (class "Default")
      (node (ref "J11") (pin "1") (pinfunction "1_1") (pintype "passive"))
      (node (ref "R4") (pin "2") (pinfunction "2_2") (pintype "passive"))
    )
    (net (code "78") (name "Net-(J15-Pad3)") (class "Default")
      (node (ref "J15") (pin "3") (pinfunction "3_3") (pintype "passive"))
      (node (ref "R5") (pin "2") (pinfunction "2_2") (pintype "passive"))
    )
    (net (code "79") (name "Net-(J15-Pad15)") (class "Default")
      (node (ref "J15") (pin "15") (pinfunction "15_15") (pintype "passive"))
      (node (ref "R6") (pin "1") (pinfunction "1_1") (pintype "passive"))
    )
    (net (code "80") (name "unconnected-(IC2-CBUS0-Pad23)") (class "Default")
      (node (ref "IC2") (pin "23") (pinfunction "CBUS0_23") (pintype "passive"))
    )
    (net (code "81") (name "unconnected-(IC2-CBUS1-Pad22)") (class "Default")
      (node (ref "IC2") (pin "22") (pinfunction "CBUS1_22") (pintype "passive"))
    )
    (net (code "82") (name "unconnected-(IC2-CBUS2-Pad13)") (class "Default")
      (node (ref "IC2") (pin "13") (pinfunction "CBUS2_13") (pintype "passive"))
    )
    (net (code "83") (name "unconnected-(IC2-CBUS3-Pad14)") (class "Default")
      (node (ref "IC2") (pin "14") (pinfunction "CBUS3_14") (pintype "passive"))
    )
    (net (code "84") (name "unconnected-(IC2-CBUS4-Pad12)") (class "Default")
      (node (ref "IC2") (pin "12") (pinfunction "CBUS4_12") (pintype "passive"))
    )
    (net (code "85") (name "unconnected-(IC2-CTS#-Pad11)") (class "Default")
      (node (ref "IC2") (pin "11") (pinfunction "CTS#_11") (pintype "passive"))
    )
    (net (code "86") (name "unconnected-(IC2-DCD#-Pad10)") (class "Default")
      (node (ref "IC2") (pin "10") (pinfunction "DCD#_10") (pintype "passive"))
    )
    (net (code "87") (name "unconnected-(IC2-DSR#-Pad9)") (class "Default")
      (node (ref "IC2") (pin "9") (pinfunction "DSR#_9") (pintype "passive"))
    )
    (net (code "88") (name "unconnected-(IC2-DTR#-Pad2)") (class "Default")
      (node (ref "IC2") (pin "2") (pinfunction "DTR#_2") (pintype "passive"))
    )
    (net (code "89") (name "unconnected-(IC2-NC-Pad8)") (class "Default")
      (node (ref "IC2") (pin "8") (pinfunction "NC_8") (pintype "passive"))
    )
    (net (code "90") (name "unconnected-(IC2-NC-Pad24)") (class "Default")
      (node (ref "IC2") (pin "24") (pinfunction "NC_24") (pintype "passive"))
    )
    (net (code "91") (name "unconnected-(IC2-OSCI-Pad27)") (class "Default")
      (node (ref "IC2") (pin "27") (pinfunction "OSCI_27") (pintype "passive"))
    )
    (net (code "92") (name "unconnected-(IC2-OSCO-Pad28)") (class "Default")
      (node (ref "IC2") (pin "28") (pinfunction "OSCO_28") (pintype "passive"))
    )
    (net (code "93") (name "unconnected-(IC2-RESET#-Pad19)") (class "Default")
      (node (ref "IC2") (pin "19") (pinfunction "RESET#_19") (pintype "passive"))
    )
    (net (code "94") (name "unconnected-(IC2-RI#-Pad6)") (class "Default")
      (node (ref "IC2") (pin "6") (pinfunction "RI#_6") (pintype "passive"))
    )
    (net (code "95") (name "unconnected-(IC2-RTS#-Pad3)") (class "Default")
      (node (ref "IC2") (pin "3") (pinfunction "RTS#_3") (pintype "passive"))
    )
    (net (code "96") (name "unconnected-(IC3A-PB0_(~{SS}{slash}PCINT0)-Pad19)") (class "Default")
      (node (ref "IC3") (pin "19") (pinfunction "PB0_(~{SS}/PCINT0)_19") (pintype "passive"))
    )
    (net (code "97") (name "unconnected-(IC3A-PB4_(OC2A{slash}PCINT4)-Pad23)") (class "Default")
      (node (ref "IC3") (pin "23") (pinfunction "PB4_(OC2A/PCINT4)_23") (pintype "passive"))
    )
    (net (code "98") (name "unconnected-(IC3A-PB5_(OC1A{slash}PCINT5)-Pad24)") (class "Default")
      (node (ref "IC3") (pin "24") (pinfunction "PB5_(OC1A/PCINT5)_24") (pintype "passive"))
    )
    (net (code "99") (name "unconnected-(IC3A-PB6_(OC1B{slash}PCINT6)-Pad25)") (class "Default")
      (node (ref "IC3") (pin "25") (pinfunction "PB6_(OC1B/PCINT6)_25") (pintype "passive"))
    )
    (net (code "100") (name "unconnected-(IC3A-PB7_(OC0A{slash}OC1C{slash}PCINT7)-Pad26)") (class "Default")
      (node (ref "IC3") (pin "26") (pinfunction "PB7_(OC0A/OC1C/PCINT7)_26") (pintype "passive"))
    )
    (net (code "101") (name "unconnected-(IC3B-PE0_(RXD0{slash}PCINT8)-Pad2)") (class "Default")
      (node (ref "IC3") (pin "2") (pinfunction "PE0_(RXD0/PCINT8)_2") (pintype "passive"))
    )
    (net (code "102") (name "unconnected-(IC3B-PE2_(XCK0{slash}AIN0)-Pad4)") (class "Default")
      (node (ref "IC3") (pin "4") (pinfunction "PE2_(XCK0/AIN0)_4") (pintype "passive"))
    )
    (net (code "103") (name "unconnected-(IC3B-PE3_(OC3A{slash}AIN1)-Pad5)") (class "Default")
      (node (ref "IC3") (pin "5") (pinfunction "PE3_(OC3A/AIN1)_5") (pintype "passive"))
    )
    (net (code "104") (name "unconnected-(IC3B-PE7_(CLKO{slash}ICP3{slash}INT7)-Pad9)") (class "Default")
      (node (ref "IC3") (pin "9") (pinfunction "PE7_(CLKO/ICP3/INT7)_9") (pintype "passive"))
    )
    (net (code "105") (name "unconnected-(IC3B-PH2_(XCK2)-Pad14)") (class "Default")
      (node (ref "IC3") (pin "14") (pinfunction "PH2_(XCK2)_14") (pintype "passive"))
    )
    (net (code "106") (name "unconnected-(IC3B-PH3_(OC4A)-Pad15)") (class "Default")
      (node (ref "IC3") (pin "15") (pinfunction "PH3_(OC4A)_15") (pintype "passive"))
    )
    (net (code "107") (name "unconnected-(IC3B-PH4_(OC4B)-Pad16)") (class "Default")
      (node (ref "IC3") (pin "16") (pinfunction "PH4_(OC4B)_16") (pintype "passive"))
    )
    (net (code "108") (name "unconnected-(IC3B-PH5_(OC4C)-Pad17)") (class "Default")
      (node (ref "IC3") (pin "17") (pinfunction "PH5_(OC4C)_17") (pintype "passive"))
    )
    (net (code "109") (name "unconnected-(IC3B-PH6_(OC2B)-Pad18)") (class "Default")
      (node (ref "IC3") (pin "18") (pinfunction "PH6_(OC2B)_18") (pintype "passive"))
    )
    (net (code "110") (name "unconnected-(IC3B-PH7_(T4)-Pad27)") (class "Default")
      (node (ref "IC3") (pin "27") (pinfunction "PH7_(T4)_27") (pintype "passive"))
    )
    (net (code "111") (name "unconnected-(IC3C-(ALE)_PG2-Pad70)") (class "Default")
      (node (ref "IC3") (pin "70") (pinfunction "(ALE)_PG2_70") (pintype "passive"))
    )
    (net (code "112") (name "unconnected-(IC3C-(OC0B)_PG5-Pad1)") (class "Default")
      (node (ref "IC3") (pin "1") (pinfunction "(OC0B)_PG5_1") (pintype "passive"))
    )
    (net (code "113") (name "unconnected-(IC3C-(TOSC1)_PG4-Pad29)") (class "Default")
      (node (ref "IC3") (pin "29") (pinfunction "(TOSC1)_PG4_29") (pintype "passive"))
    )
    (net (code "114") (name "unconnected-(IC3C-(TOSC2)_PG3-Pad28)") (class "Default")
      (node (ref "IC3") (pin "28") (pinfunction "(TOSC2)_PG3_28") (pintype "passive"))
    )
    (net (code "115") (name "unconnected-(IC3C-(~{RD})_PG1-Pad52)") (class "Default")
      (node (ref "IC3") (pin "52") (pinfunction "(~{RD})_PG1_52") (pintype "passive"))
    )
    (net (code "116") (name "unconnected-(IC3C-(~{WR})_PG0-Pad51)") (class "Default")
      (node (ref "IC3") (pin "51") (pinfunction "(~{WR})_PG0_51") (pintype "passive"))
    )
    (net (code "117") (name "unconnected-(IC3C-PL7-Pad42)") (class "Default")
      (node (ref "IC3") (pin "42") (pinfunction "PL7_42") (pintype "passive"))
    )
    (net (code "118") (name "unconnected-(IC4-DO-Pad1)") (class "Default")
      (node (ref "IC4") (pin "1") (pinfunction "DO_1") (pintype "passive"))
    )
    (net (code "119") (name "unconnected-(J19-Pad1)") (class "Default")
      (node (ref "J19") (pin "1") (pinfunction "1_1") (pintype "passive"))
    )
    (net (code "120") (name "unconnected-(J19-Pad2)") (class "Default")
      (node (ref "J19") (pin "2") (pinfunction "2_2") (pintype "passive"))
    )
  )
)
